# GasSensorCentral_v2_4.net
KiCad netlist of a schematic drawn in EAGLE
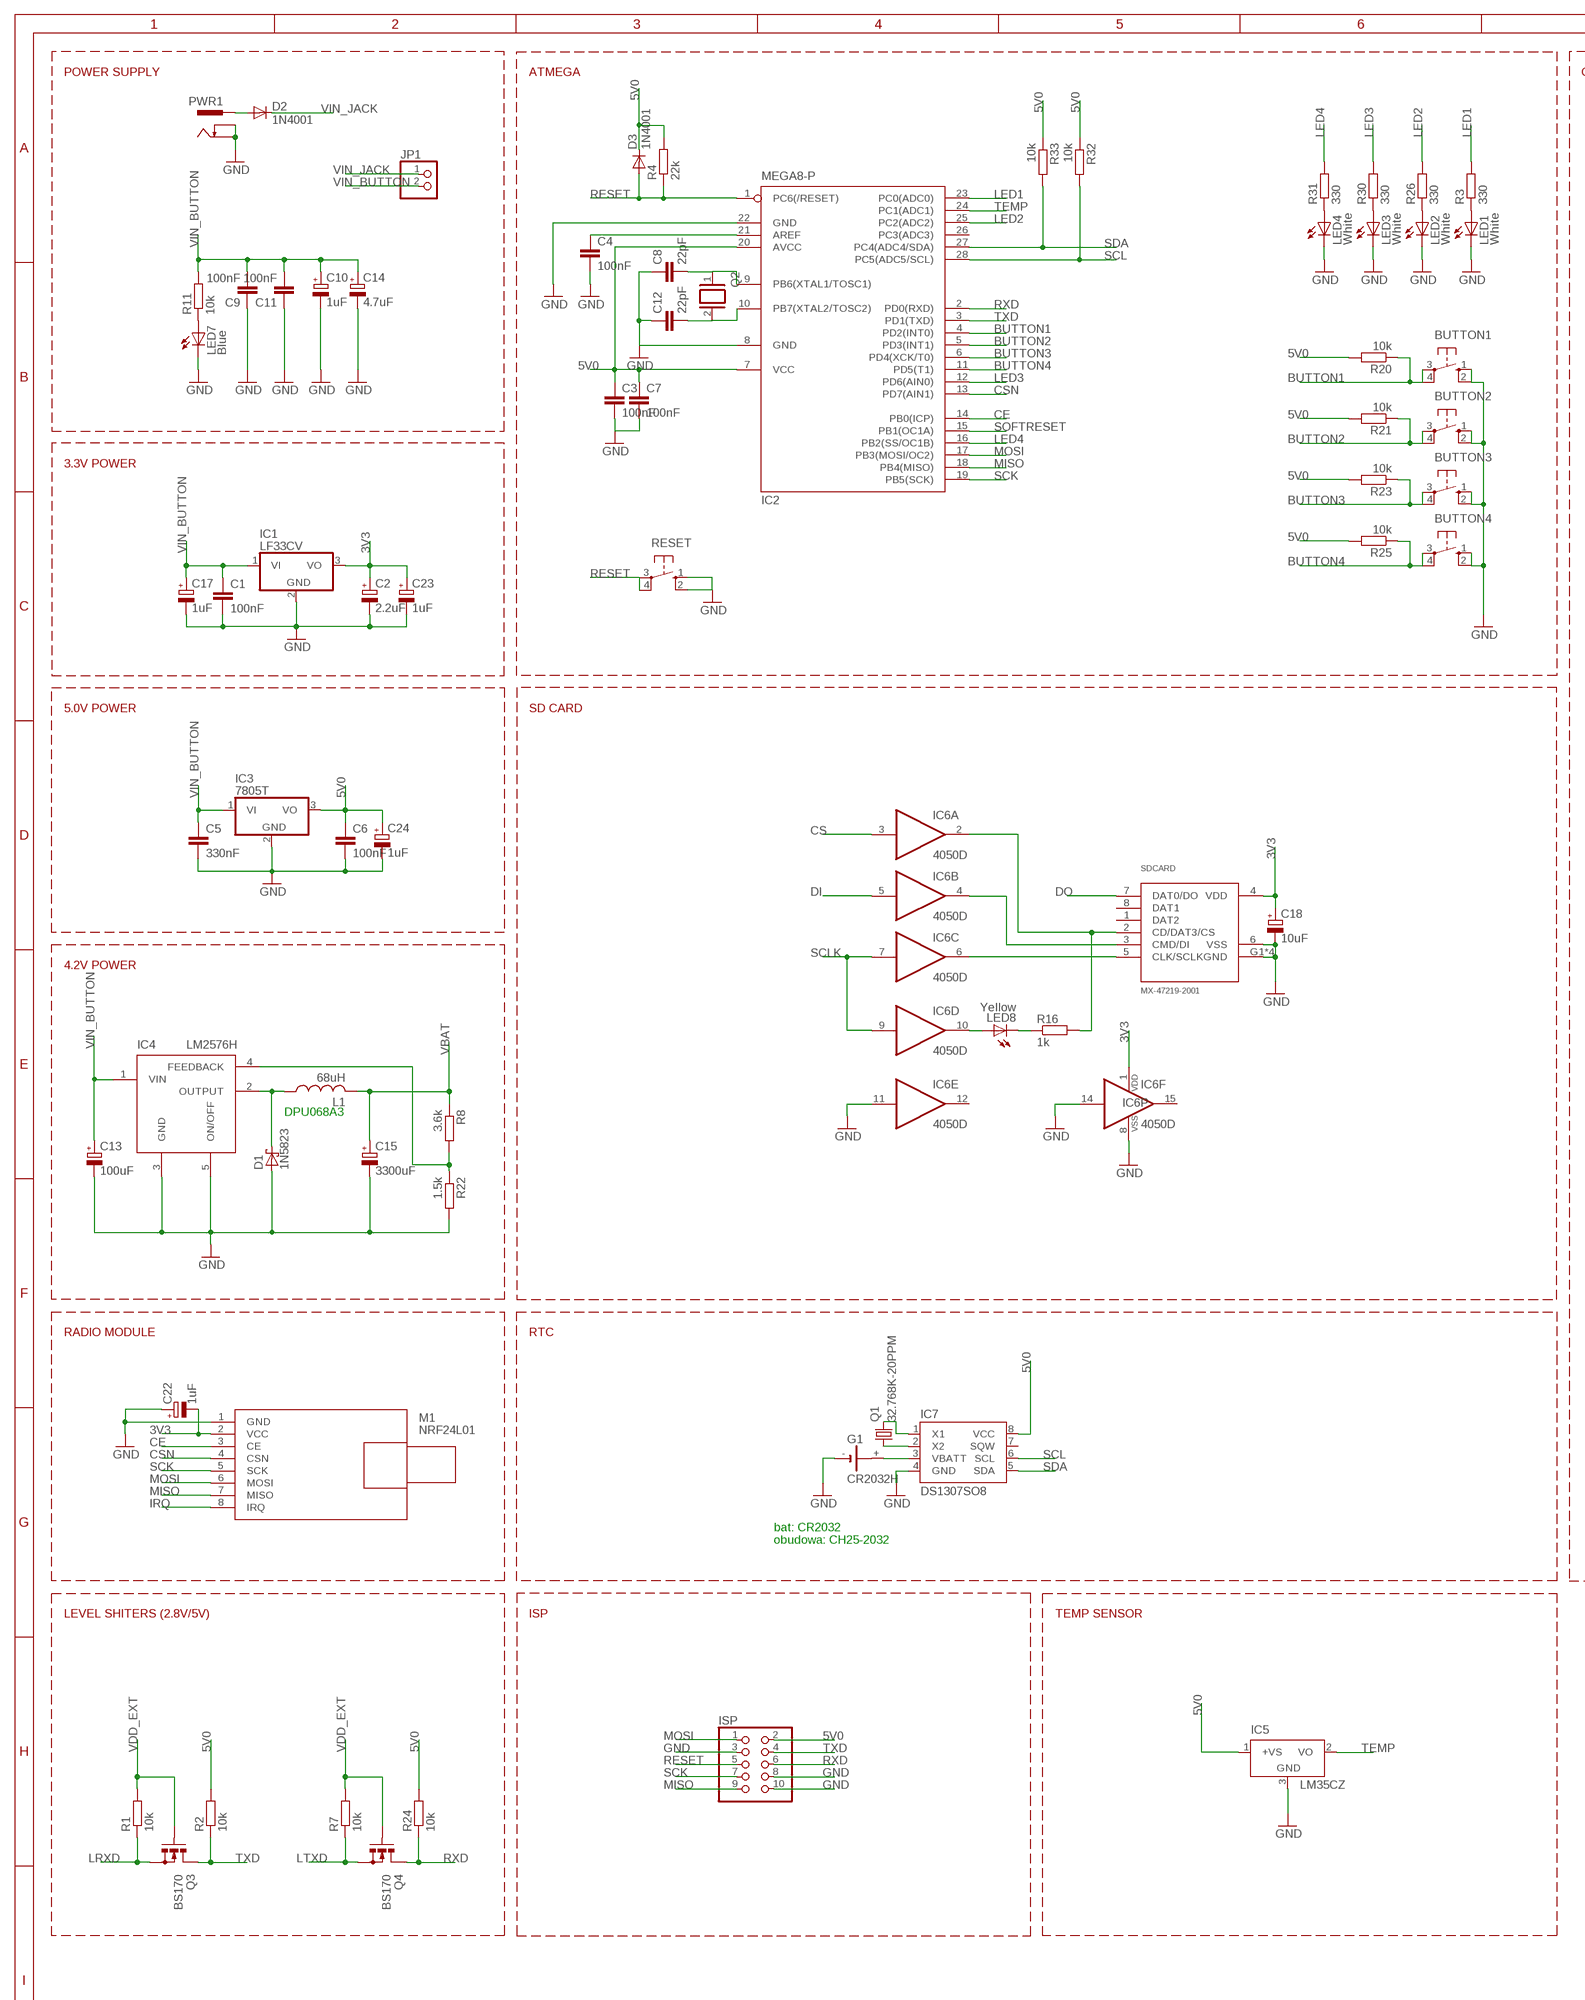
[diagram p0: schematic, sheet 1, part 1 of 2]
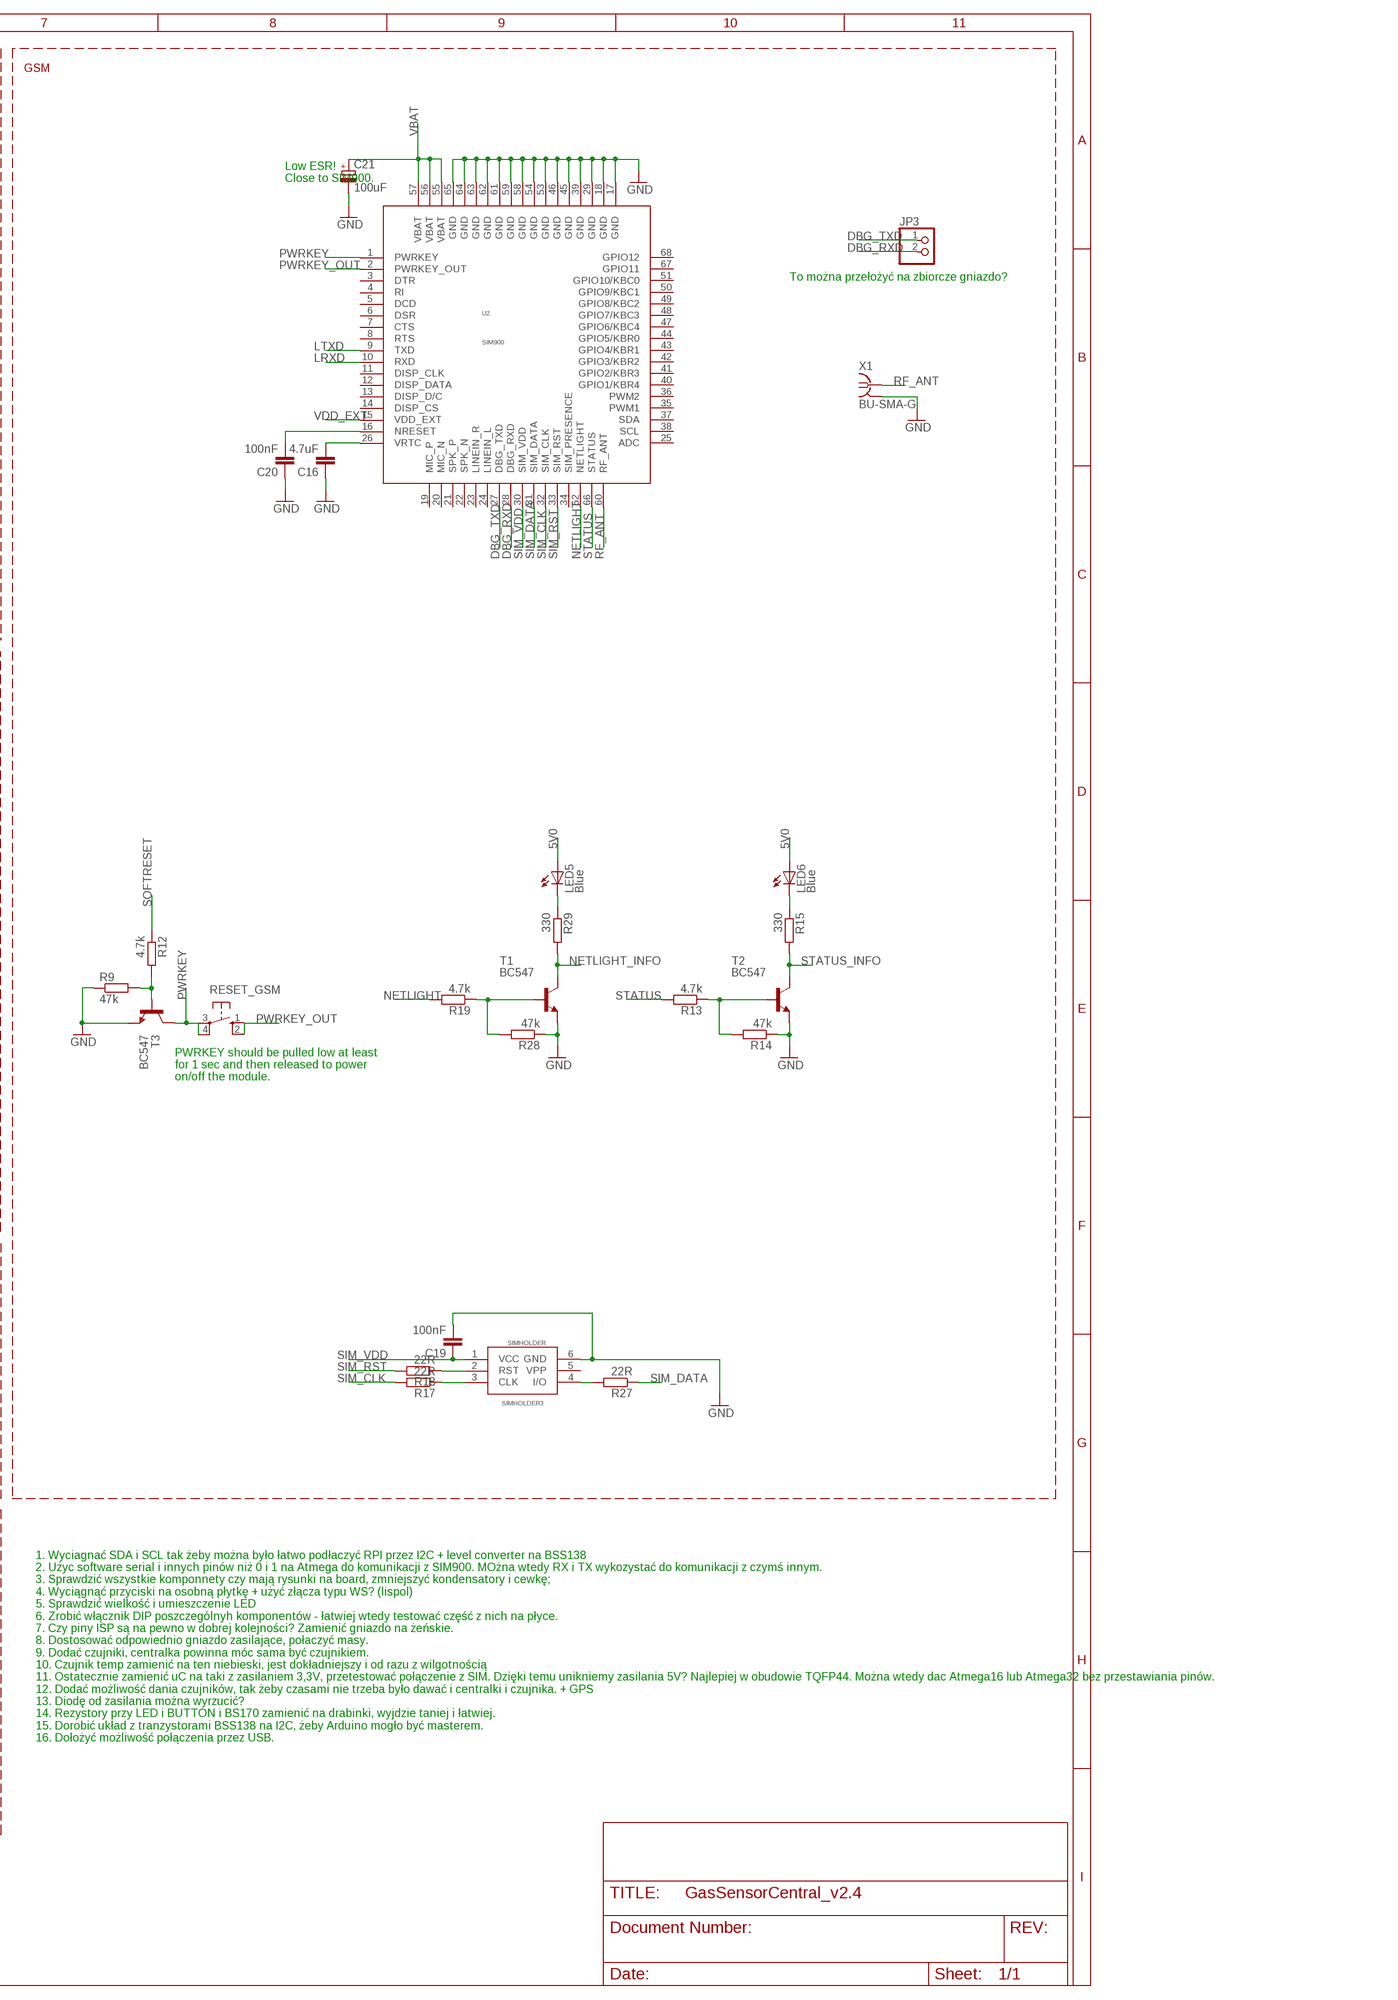
[diagram p1: schematic, sheet 1, part 2 of 2]

(export (version "E")
  (design (tool "Eeschema 10.0.6"))
  (components
    (comp (ref "BUTTON1")
      (value "10-XX")
      (footprint "eagle-import:B3F-10XX")
      (fields (field (name "MPN") "B3F-1000"))
      (libsource (lib "eagle-import") (part "10-XX"))
    )
    (comp (ref "BUTTON2")
      (value "10-XX")
      (footprint "eagle-import:B3F-10XX")
      (fields (field (name "MPN") "B3F-1000"))
      (libsource (lib "eagle-import") (part "10-XX"))
    )
    (comp (ref "BUTTON3")
      (value "10-XX")
      (footprint "eagle-import:B3F-10XX")
      (fields (field (name "MPN") "B3F-1000"))
      (libsource (lib "eagle-import") (part "10-XX"))
    )
    (comp (ref "BUTTON4")
      (value "10-XX")
      (footprint "eagle-import:B3F-10XX")
      (fields (field (name "MPN") "B3F-1000"))
      (libsource (lib "eagle-import") (part "10-XX"))
    )
    (comp (ref "C1")
      (value "100nF")
      (footprint "eagle-import:C025-025X050")
      (libsource (lib "eagle-import") (part "C-EU025-025X050"))
    )
    (comp (ref "C2")
      (value "2.2uF")
      (footprint "eagle-import:E2,5-5")
      (libsource (lib "eagle-import") (part "CPOL-EUE2.5-5"))
    )
    (comp (ref "C3")
      (value "100nF")
      (footprint "eagle-import:C025-025X050")
      (libsource (lib "eagle-import") (part "C-EU025-025X050"))
    )
    (comp (ref "C4")
      (value "100nF")
      (footprint "eagle-import:C025-025X050")
      (libsource (lib "eagle-import") (part "C-EU025-025X050"))
    )
    (comp (ref "C5")
      (value "330nF")
      (footprint "eagle-import:C025-025X050")
      (libsource (lib "eagle-import") (part "C-EU025-025X050"))
    )
    (comp (ref "C6")
      (value "100nF")
      (footprint "eagle-import:C025-025X050")
      (libsource (lib "eagle-import") (part "C-EU025-025X050"))
    )
    (comp (ref "C7")
      (value "100nF")
      (footprint "eagle-import:C025-025X050")
      (libsource (lib "eagle-import") (part "C-EU025-025X050"))
    )
    (comp (ref "C8")
      (value "22pF")
      (footprint "eagle-import:C025-025X050")
      (libsource (lib "eagle-import") (part "C-EU025-025X050"))
    )
    (comp (ref "C9")
      (value "100nF")
      (footprint "eagle-import:C025-025X050")
      (libsource (lib "eagle-import") (part "C-EU025-025X050"))
    )
    (comp (ref "C10")
      (value "1uF")
      (footprint "eagle-import:E2,5-5")
      (libsource (lib "eagle-import") (part "CPOL-EUE2.5-5"))
    )
    (comp (ref "C11")
      (value "100nF")
      (footprint "eagle-import:C025-025X050")
      (libsource (lib "eagle-import") (part "C-EU025-025X050"))
    )
    (comp (ref "C12")
      (value "22pF")
      (footprint "eagle-import:C025-025X050")
      (libsource (lib "eagle-import") (part "C-EU025-025X050"))
    )
    (comp (ref "C13")
      (value "100uF")
      (footprint "eagle-import:E2,5-5")
      (libsource (lib "eagle-import") (part "CPOL-EUE2.5-5"))
    )
    (comp (ref "C14")
      (value "4.7uF")
      (footprint "eagle-import:E2,5-5")
      (libsource (lib "eagle-import") (part "CPOL-EUE2.5-5"))
    )
    (comp (ref "C15")
      (value "3300uF")
      (footprint "eagle-import:E5-13")
      (libsource (lib "eagle-import") (part "CPOL-EUE5-13"))
    )
    (comp (ref "C16")
      (value "4.7uF")
      (footprint "eagle-import:C025-025X050")
      (libsource (lib "eagle-import") (part "C-EU025-025X050"))
    )
    (comp (ref "C17")
      (value "1uF")
      (footprint "eagle-import:E2,5-5")
      (libsource (lib "eagle-import") (part "CPOL-EUE2.5-5"))
    )
    (comp (ref "C18")
      (value "10uF")
      (footprint "eagle-import:E2,5-5")
      (libsource (lib "eagle-import") (part "CPOL-EUE2.5-5"))
    )
    (comp (ref "C19")
      (value "100nF")
      (footprint "eagle-import:C025-025X050")
      (libsource (lib "eagle-import") (part "C-EU025-025X050"))
    )
    (comp (ref "C20")
      (value "100nF")
      (footprint "eagle-import:C025-025X050")
      (libsource (lib "eagle-import") (part "C-EU025-025X050"))
    )
    (comp (ref "C21")
      (value "100uF")
      (footprint "eagle-import:E2,5-5")
      (libsource (lib "eagle-import") (part "CPOL-EUE2.5-5"))
    )
    (comp (ref "C22")
      (value "1uF")
      (footprint "eagle-import:E2,5-5")
      (libsource (lib "eagle-import") (part "CPOL-EUE2.5-5"))
    )
    (comp (ref "C23")
      (value "1uF")
      (footprint "eagle-import:E2,5-5")
      (libsource (lib "eagle-import") (part "CPOL-EUE2.5-5"))
    )
    (comp (ref "C24")
      (value "1uF")
      (footprint "eagle-import:E2,5-5")
      (libsource (lib "eagle-import") (part "CPOL-EUE2.5-5"))
    )
    (comp (ref "D1")
      (value "1N5823")
      (footprint "eagle-import:DO41-7.6")
      (libsource (lib "eagle-import") (part "1N5817-B"))
    )
    (comp (ref "D2")
      (value "1N4001")
      (footprint "eagle-import:DO41-10")
      (libsource (lib "eagle-import") (part "1N4004"))
    )
    (comp (ref "D3")
      (value "1N4001")
      (footprint "eagle-import:DO41-10")
      (libsource (lib "eagle-import") (part "1N4004"))
    )
    (comp (ref "G1")
      (value "CR2032H")
      (footprint "eagle-import:CR2032H")
      (libsource (lib "eagle-import") (part "CR2032H"))
    )
    (comp (ref "IC1")
      (value "LF33CV")
      (footprint "eagle-import:TO220H")
      (libsource (lib "eagle-import") (part "78T05"))
    )
    (comp (ref "IC2")
      (value "MEGA8-P")
      (footprint "eagle-import:DIL28-3")
      (libsource (lib "eagle-import") (part "MEGA8-P"))
    )
    (comp (ref "IC3")
      (value "7805T")
      (footprint "eagle-import:TO220H")
      (libsource (lib "eagle-import") (part "78T05"))
    )
    (comp (ref "IC4")
      (value "LM2576H")
      (footprint "eagle-import:TO220-52")
      (libsource (lib "eagle-import") (part "LM2576H"))
    )
    (comp (ref "IC5")
      (value "LM35CZ")
      (footprint "eagle-import:TO92")
      (libsource (lib "eagle-import") (part "LM35CZ"))
    )
    (comp (ref "IC6")
      (value "4050D")
      (footprint "eagle-import:SO16")
      (libsource (lib "eagle-import") (part "4050D"))
    )
    (comp (ref "IC7")
      (value "DS1307SO8")
      (footprint "eagle-import:SO08")
      (libsource (lib "eagle-import") (part "DS1307SO8"))
    )
    (comp (ref "ISP")
      (value "PINHD-2X5")
      (footprint "eagle-import:2X05")
      (libsource (lib "eagle-import") (part "PINHD-2X5"))
    )
    (comp (ref "JP1")
      (value "PINHD-1X2")
      (footprint "eagle-import:1X02")
      (libsource (lib "eagle-import") (part "PINHD-1X2"))
    )
    (comp (ref "JP3")
      (value "PINHD-1X2")
      (footprint "eagle-import:1X02")
      (libsource (lib "eagle-import") (part "PINHD-1X2"))
    )
    (comp (ref "L1")
      (value "68uH")
      (footprint "eagle-import:TJ4-U1")
      (libsource (lib "eagle-import") (part "L-USTJ4-U1"))
    )
    (comp (ref "LED1")
      (value "White")
      (footprint "eagle-import:LED3MM")
      (libsource (lib "eagle-import") (part "LED3MM"))
    )
    (comp (ref "LED2")
      (value "White")
      (footprint "eagle-import:LED3MM")
      (libsource (lib "eagle-import") (part "LED3MM"))
    )
    (comp (ref "LED3")
      (value "White")
      (footprint "eagle-import:LED3MM")
      (libsource (lib "eagle-import") (part "LED3MM"))
    )
    (comp (ref "LED4")
      (value "White")
      (footprint "eagle-import:LED3MM")
      (libsource (lib "eagle-import") (part "LED3MM"))
    )
    (comp (ref "LED5")
      (value "Blue")
      (footprint "eagle-import:LED3MM")
      (libsource (lib "eagle-import") (part "LED3MM"))
    )
    (comp (ref "LED6")
      (value "Blue")
      (footprint "eagle-import:LED3MM")
      (libsource (lib "eagle-import") (part "LED3MM"))
    )
    (comp (ref "LED7")
      (value "Blue")
      (footprint "eagle-import:LED3MM")
      (libsource (lib "eagle-import") (part "LED3MM"))
    )
    (comp (ref "LED8")
      (value "Yellow")
      (footprint "eagle-import:LED3MM")
      (libsource (lib "eagle-import") (part "LED3MM"))
    )
    (comp (ref "M1")
      (value "NRF24L01")
      (footprint "eagle-import:WIRELESS-NRD24L01-PA-EXT")
      (libsource (lib "eagle-import") (part "WIRELESS-NRF24L01-PA-EXT"))
    )
    (comp (ref "PWR1")
      (value "PWR-JAKPWR_JACK_UNI_MILLING")
      (footprint "eagle-import:PWR_JACK_UNI_MILLING")
      (libsource (lib "eagle-import") (part "PWR-JAKPWR_JACK_UNI_MILLING"))
    )
    (comp (ref "Q1")
      (value "32.768K-20PPM")
      (footprint "eagle-import:TC26V")
      (libsource (lib "eagle-import") (part "CRYSTALTC26V"))
    )
    (comp (ref "Q2")
      (value "XTAL/S")
      (footprint "eagle-import:QS")
      (libsource (lib "eagle-import") (part "XTAL/S"))
    )
    (comp (ref "Q3")
      (value "BS170")
      (footprint "eagle-import:SOT54E")
      (libsource (lib "eagle-import") (part "BS170"))
    )
    (comp (ref "Q4")
      (value "BS170")
      (footprint "eagle-import:SOT54E")
      (libsource (lib "eagle-import") (part "BS170"))
    )
    (comp (ref "R1")
      (value "10k")
      (footprint "eagle-import:0207_10")
      (libsource (lib "eagle-import") (part "R-EU_0207/10"))
    )
    (comp (ref "R2")
      (value "10k")
      (footprint "eagle-import:0207_10")
      (libsource (lib "eagle-import") (part "R-EU_0207/10"))
    )
    (comp (ref "R3")
      (value "330")
      (footprint "eagle-import:0207_10")
      (libsource (lib "eagle-import") (part "R-EU_0207/10"))
    )
    (comp (ref "R4")
      (value "22k")
      (footprint "eagle-import:0207_10")
      (libsource (lib "eagle-import") (part "R-EU_0207/10"))
    )
    (comp (ref "R7")
      (value "10k")
      (footprint "eagle-import:0207_10")
      (libsource (lib "eagle-import") (part "R-EU_0207/10"))
    )
    (comp (ref "R8")
      (value "3.6k")
      (footprint "eagle-import:0207_10")
      (libsource (lib "eagle-import") (part "R-EU_0207/10"))
    )
    (comp (ref "R9")
      (value "47k")
      (footprint "eagle-import:0207_10")
      (libsource (lib "eagle-import") (part "R-EU_0207/10"))
    )
    (comp (ref "R11")
      (value "10k")
      (footprint "eagle-import:0207_10")
      (libsource (lib "eagle-import") (part "R-EU_0207/10"))
    )
    (comp (ref "R12")
      (value "4.7k")
      (footprint "eagle-import:0207_10")
      (libsource (lib "eagle-import") (part "R-EU_0207/10"))
    )
    (comp (ref "R13")
      (value "4.7k")
      (footprint "eagle-import:0207_10")
      (libsource (lib "eagle-import") (part "R-EU_0207/10"))
    )
    (comp (ref "R14")
      (value "47k")
      (footprint "eagle-import:0207_10")
      (libsource (lib "eagle-import") (part "R-EU_0207/10"))
    )
    (comp (ref "R15")
      (value "330")
      (footprint "eagle-import:0207_10")
      (libsource (lib "eagle-import") (part "R-EU_0207/10"))
    )
    (comp (ref "R16")
      (value "1k")
      (footprint "eagle-import:0207_10")
      (libsource (lib "eagle-import") (part "R-EU_0207/10"))
    )
    (comp (ref "R17")
      (value "22R")
      (footprint "eagle-import:0207_10")
      (libsource (lib "eagle-import") (part "R-EU_0207/10"))
    )
    (comp (ref "R18")
      (value "22R")
      (footprint "eagle-import:0207_10")
      (libsource (lib "eagle-import") (part "R-EU_0207/10"))
    )
    (comp (ref "R19")
      (value "4.7k")
      (footprint "eagle-import:0207_10")
      (libsource (lib "eagle-import") (part "R-EU_0207/10"))
    )
    (comp (ref "R20")
      (value "10k")
      (footprint "eagle-import:0207_10")
      (libsource (lib "eagle-import") (part "R-EU_0207/10"))
    )
    (comp (ref "R21")
      (value "10k")
      (footprint "eagle-import:0207_10")
      (libsource (lib "eagle-import") (part "R-EU_0207/10"))
    )
    (comp (ref "R22")
      (value "1.5k")
      (footprint "eagle-import:0207_10")
      (libsource (lib "eagle-import") (part "R-EU_0207/10"))
    )
    (comp (ref "R23")
      (value "10k")
      (footprint "eagle-import:0207_10")
      (libsource (lib "eagle-import") (part "R-EU_0207/10"))
    )
    (comp (ref "R24")
      (value "10k")
      (footprint "eagle-import:0207_10")
      (libsource (lib "eagle-import") (part "R-EU_0207/10"))
    )
    (comp (ref "R25")
      (value "10k")
      (footprint "eagle-import:0207_10")
      (libsource (lib "eagle-import") (part "R-EU_0207/10"))
    )
    (comp (ref "R26")
      (value "330")
      (footprint "eagle-import:0207_10")
      (libsource (lib "eagle-import") (part "R-EU_0207/10"))
    )
    (comp (ref "R27")
      (value "22R")
      (footprint "eagle-import:0207_10")
      (libsource (lib "eagle-import") (part "R-EU_0207/10"))
    )
    (comp (ref "R28")
      (value "47k")
      (footprint "eagle-import:0207_10")
      (libsource (lib "eagle-import") (part "R-EU_0207/10"))
    )
    (comp (ref "R29")
      (value "330")
      (footprint "eagle-import:0207_10")
      (libsource (lib "eagle-import") (part "R-EU_0207/10"))
    )
    (comp (ref "R30")
      (value "330")
      (footprint "eagle-import:0207_10")
      (libsource (lib "eagle-import") (part "R-EU_0207/10"))
    )
    (comp (ref "R31")
      (value "330")
      (footprint "eagle-import:0207_10")
      (libsource (lib "eagle-import") (part "R-EU_0207/10"))
    )
    (comp (ref "R32")
      (value "10k")
      (footprint "eagle-import:0207_10")
      (libsource (lib "eagle-import") (part "R-EU_0207/10"))
    )
    (comp (ref "R33")
      (value "10k")
      (footprint "eagle-import:0207_10")
      (libsource (lib "eagle-import") (part "R-EU_0207/10"))
    )
    (comp (ref "RESET")
      (value "10-XX")
      (footprint "eagle-import:B3F-10XX")
      (fields (field (name "MPN") "B3F-1000"))
      (libsource (lib "eagle-import") (part "10-XX"))
    )
    (comp (ref "RESET_GSM")
      (value "10-XX")
      (footprint "eagle-import:B3F-10XX")
      (fields (field (name "MPN") "B3F-1000"))
      (libsource (lib "eagle-import") (part "10-XX"))
    )
    (comp (ref "SDCARD")
      (value "MX-47219-2001")
      (footprint "eagle-import:MX-47219-2001")
      (libsource (lib "eagle-import") (part "MX-47219-2001"))
    )
    (comp (ref "SIMHOLDER")
      (value "SIMHOLDER3")
      (footprint "eagle-import:SIMHOLDER3")
      (libsource (lib "eagle-import") (part "SIMHOLDER3"))
    )
    (comp (ref "T1")
      (value "BC547")
      (footprint "eagle-import:TO92")
      (libsource (lib "eagle-import") (part "BC547"))
    )
    (comp (ref "T2")
      (value "BC547")
      (footprint "eagle-import:TO92")
      (libsource (lib "eagle-import") (part "BC547"))
    )
    (comp (ref "T3")
      (value "BC547")
      (footprint "eagle-import:TO92")
      (libsource (lib "eagle-import") (part "BC547"))
    )
    (comp (ref "U2")
      (value "SIM900")
      (footprint "eagle-import:SIM900")
      (libsource (lib "eagle-import") (part "SIM900"))
    )
    (comp (ref "X1")
      (value "BU-SMA-G")
      (footprint "eagle-import:BU-SMA-G")
      (libsource (lib "eagle-import") (part "BU-SMA-G"))
    )
  )
  (nets
    (net (code "1") (name "/3V3") (class "Default")
      (node (ref "C18") (pin "+") (pinfunction "+_+") (pintype "passive"))
      (node (ref "C2") (pin "+") (pinfunction "+_+") (pintype "passive"))
      (node (ref "C22") (pin "-") (pinfunction "-_-") (pintype "passive"))
      (node (ref "C23") (pin "+") (pinfunction "+_+") (pintype "passive"))
      (node (ref "IC1") (pin "3") (pinfunction "VO_3") (pintype "passive"))
      (node (ref "IC6") (pin "1") (pinfunction "VDD_1") (pintype "power_in"))
      (node (ref "M1") (pin "2") (pinfunction "VCC_2") (pintype "power_in"))
      (node (ref "SDCARD") (pin "4") (pinfunction "VDD_4") (pintype "bidirectional"))
    )
    (net (code "2") (name "/5V0") (class "Default")
      (node (ref "C24") (pin "+") (pinfunction "+_+") (pintype "passive"))
      (node (ref "C3") (pin "1") (pinfunction "1_1") (pintype "passive"))
      (node (ref "C6") (pin "1") (pinfunction "1_1") (pintype "passive"))
      (node (ref "C7") (pin "1") (pinfunction "1_1") (pintype "passive"))
      (node (ref "D3") (pin "C") (pinfunction "C_C") (pintype "passive"))
      (node (ref "IC2") (pin "20") (pinfunction "AVCC_20") (pintype "power_in"))
      (node (ref "IC2") (pin "7") (pinfunction "VCC_7") (pintype "power_in"))
      (node (ref "IC3") (pin "3") (pinfunction "VO_3") (pintype "passive"))
      (node (ref "IC5") (pin "1") (pinfunction "+VS_1") (pintype "input"))
      (node (ref "IC7") (pin "8") (pinfunction "VCC_8") (pintype "bidirectional"))
      (node (ref "ISP") (pin "2") (pinfunction "2_2") (pintype "passive"))
      (node (ref "LED5") (pin "A") (pinfunction "A_A") (pintype "passive"))
      (node (ref "LED6") (pin "A") (pinfunction "A_A") (pintype "passive"))
      (node (ref "R2") (pin "2") (pinfunction "2_2") (pintype "passive"))
      (node (ref "R20") (pin "2") (pinfunction "2_2") (pintype "passive"))
      (node (ref "R21") (pin "2") (pinfunction "2_2") (pintype "passive"))
      (node (ref "R23") (pin "2") (pinfunction "2_2") (pintype "passive"))
      (node (ref "R24") (pin "2") (pinfunction "2_2") (pintype "passive"))
      (node (ref "R25") (pin "2") (pinfunction "2_2") (pintype "passive"))
      (node (ref "R32") (pin "1") (pinfunction "1_1") (pintype "passive"))
      (node (ref "R33") (pin "1") (pinfunction "1_1") (pintype "passive"))
      (node (ref "R4") (pin "2") (pinfunction "2_2") (pintype "passive"))
    )
    (net (code "3") (name "/BUTTON1") (class "Default")
      (node (ref "BUTTON1") (pin "3") (pinfunction "P_3") (pintype "passive"))
      (node (ref "BUTTON1") (pin "4") (pinfunction "P1_4") (pintype "passive"))
      (node (ref "IC2") (pin "4") (pinfunction "PD2(INT0)_4") (pintype "bidirectional"))
      (node (ref "R20") (pin "1") (pinfunction "1_1") (pintype "passive"))
    )
    (net (code "4") (name "/BUTTON2") (class "Default")
      (node (ref "BUTTON2") (pin "3") (pinfunction "P_3") (pintype "passive"))
      (node (ref "BUTTON2") (pin "4") (pinfunction "P1_4") (pintype "passive"))
      (node (ref "IC2") (pin "5") (pinfunction "PD3(INT1)_5") (pintype "bidirectional"))
      (node (ref "R21") (pin "1") (pinfunction "1_1") (pintype "passive"))
    )
    (net (code "5") (name "/BUTTON3") (class "Default")
      (node (ref "BUTTON3") (pin "3") (pinfunction "P_3") (pintype "passive"))
      (node (ref "BUTTON3") (pin "4") (pinfunction "P1_4") (pintype "passive"))
      (node (ref "IC2") (pin "6") (pinfunction "PD4(XCK/T0)_6") (pintype "bidirectional"))
      (node (ref "R23") (pin "1") (pinfunction "1_1") (pintype "passive"))
    )
    (net (code "6") (name "/BUTTON4") (class "Default")
      (node (ref "BUTTON4") (pin "3") (pinfunction "P_3") (pintype "passive"))
      (node (ref "BUTTON4") (pin "4") (pinfunction "P1_4") (pintype "passive"))
      (node (ref "IC2") (pin "11") (pinfunction "PD5(T1)_11") (pintype "bidirectional"))
      (node (ref "R25") (pin "1") (pinfunction "1_1") (pintype "passive"))
    )
    (net (code "7") (name "/CE") (class "Default")
      (node (ref "IC2") (pin "14") (pinfunction "PB0(ICP)_14") (pintype "bidirectional"))
      (node (ref "M1") (pin "3") (pinfunction "CE_3") (pintype "bidirectional"))
    )
    (net (code "8") (name "/CS") (class "Default")
      (node (ref "IC6") (pin "3") (pinfunction "I_3") (pintype "input"))
    )
    (net (code "9") (name "/CSN") (class "Default")
      (node (ref "IC2") (pin "13") (pinfunction "PD7(AIN1)_13") (pintype "bidirectional"))
      (node (ref "M1") (pin "4") (pinfunction "CSN_4") (pintype "bidirectional"))
    )
    (net (code "10") (name "/DBG_RXD") (class "Default")
      (node (ref "JP3") (pin "2") (pinfunction "2_2") (pintype "passive"))
      (node (ref "U2") (pin "28") (pinfunction "DBG_RXD_28") (pintype "input"))
    )
    (net (code "11") (name "/DBG_TXD") (class "Default")
      (node (ref "JP3") (pin "1") (pinfunction "1_1") (pintype "passive"))
      (node (ref "U2") (pin "27") (pinfunction "DBG_TXD_27") (pintype "output"))
    )
    (net (code "12") (name "/DI") (class "Default")
      (node (ref "IC6") (pin "5") (pinfunction "I_5") (pintype "input"))
    )
    (net (code "13") (name "/DO") (class "Default")
      (node (ref "SDCARD") (pin "7") (pinfunction "DAT0/DO_7") (pintype "bidirectional"))
    )
    (net (code "14") (name "/IRQ") (class "Default")
      (node (ref "M1") (pin "8") (pinfunction "IRQ_8") (pintype "bidirectional"))
    )
    (net (code "15") (name "/LED1") (class "Default")
      (node (ref "IC2") (pin "23") (pinfunction "PC0(ADC0)_23") (pintype "bidirectional"))
      (node (ref "R3") (pin "2") (pinfunction "2_2") (pintype "passive"))
    )
    (net (code "16") (name "/LED2") (class "Default")
      (node (ref "IC2") (pin "25") (pinfunction "PC2(ADC2)_25") (pintype "bidirectional"))
      (node (ref "R26") (pin "2") (pinfunction "2_2") (pintype "passive"))
    )
    (net (code "17") (name "/LED3") (class "Default")
      (node (ref "IC2") (pin "12") (pinfunction "PD6(AIN0)_12") (pintype "bidirectional"))
      (node (ref "R30") (pin "2") (pinfunction "2_2") (pintype "passive"))
    )
    (net (code "18") (name "/LED4") (class "Default")
      (node (ref "IC2") (pin "16") (pinfunction "PB2(SS/OC1B)_16") (pintype "bidirectional"))
      (node (ref "R31") (pin "2") (pinfunction "2_2") (pintype "passive"))
    )
    (net (code "19") (name "/LRXD") (class "Default")
      (node (ref "Q3") (pin "S") (pinfunction "S_S") (pintype "passive"))
      (node (ref "R1") (pin "1") (pinfunction "1_1") (pintype "passive"))
      (node (ref "U2") (pin "10") (pinfunction "RXD_10") (pintype "input"))
    )
    (net (code "20") (name "/LTXD") (class "Default")
      (node (ref "Q4") (pin "S") (pinfunction "S_S") (pintype "passive"))
      (node (ref "R7") (pin "1") (pinfunction "1_1") (pintype "passive"))
      (node (ref "U2") (pin "9") (pinfunction "TXD_9") (pintype "output"))
    )
    (net (code "21") (name "/MISO") (class "Default")
      (node (ref "IC2") (pin "18") (pinfunction "PB4(MISO)_18") (pintype "bidirectional"))
      (node (ref "ISP") (pin "9") (pinfunction "9_9") (pintype "passive"))
      (node (ref "M1") (pin "7") (pinfunction "MISO_7") (pintype "bidirectional"))
    )
    (net (code "22") (name "/MOSI") (class "Default")
      (node (ref "IC2") (pin "17") (pinfunction "PB3(MOSI/OC2)_17") (pintype "bidirectional"))
      (node (ref "ISP") (pin "1") (pinfunction "1_1") (pintype "passive"))
      (node (ref "M1") (pin "6") (pinfunction "MOSI_6") (pintype "bidirectional"))
    )
    (net (code "23") (name "/NETLIGHT") (class "Default")
      (node (ref "R19") (pin "2") (pinfunction "2_2") (pintype "passive"))
      (node (ref "U2") (pin "52") (pinfunction "NETLIGHT_52") (pintype "output"))
    )
    (net (code "24") (name "/NETLIGHT_INFO") (class "Default")
      (node (ref "R29") (pin "2") (pinfunction "2_2") (pintype "passive"))
      (node (ref "T1") (pin "3") (pinfunction "C_3") (pintype "passive"))
    )
    (net (code "25") (name "/PWRKEY") (class "Default")
      (node (ref "RESET_GSM") (pin "3") (pinfunction "P_3") (pintype "passive"))
      (node (ref "RESET_GSM") (pin "4") (pinfunction "P1_4") (pintype "passive"))
      (node (ref "T3") (pin "3") (pinfunction "C_3") (pintype "passive"))
      (node (ref "U2") (pin "1") (pinfunction "PWRKEY_1") (pintype "input"))
    )
    (net (code "26") (name "/PWRKEY_OUT") (class "Default")
      (node (ref "RESET_GSM") (pin "1") (pinfunction "S_1") (pintype "passive"))
      (node (ref "RESET_GSM") (pin "2") (pinfunction "S1_2") (pintype "passive"))
      (node (ref "U2") (pin "2") (pinfunction "PWRKEY_OUT_2") (pintype "output"))
    )
    (net (code "27") (name "/RESET") (class "Default")
      (node (ref "D3") (pin "A") (pinfunction "A_A") (pintype "passive"))
      (node (ref "IC2") (pin "1") (pinfunction "PC6(/RESET)_1") (pintype "bidirectional"))
      (node (ref "ISP") (pin "5") (pinfunction "5_5") (pintype "passive"))
      (node (ref "R4") (pin "1") (pinfunction "1_1") (pintype "passive"))
      (node (ref "RESET") (pin "3") (pinfunction "P_3") (pintype "passive"))
      (node (ref "RESET") (pin "4") (pinfunction "P1_4") (pintype "passive"))
    )
    (net (code "28") (name "/RF_ANT") (class "Default")
      (node (ref "U2") (pin "60") (pinfunction "RF_ANT_60") (pintype "bidirectional"))
      (node (ref "X1") (pin "1") (pinfunction "1_1") (pintype "passive"))
    )
    (net (code "29") (name "/RXD") (class "Default")
      (node (ref "IC2") (pin "2") (pinfunction "PD0(RXD)_2") (pintype "bidirectional"))
      (node (ref "ISP") (pin "6") (pinfunction "6_6") (pintype "passive"))
      (node (ref "Q4") (pin "D") (pinfunction "D_D") (pintype "passive"))
      (node (ref "R24") (pin "1") (pinfunction "1_1") (pintype "passive"))
    )
    (net (code "30") (name "/SCK") (class "Default")
      (node (ref "IC2") (pin "19") (pinfunction "PB5(SCK)_19") (pintype "bidirectional"))
      (node (ref "ISP") (pin "7") (pinfunction "7_7") (pintype "passive"))
      (node (ref "M1") (pin "5") (pinfunction "SCK_5") (pintype "bidirectional"))
    )
    (net (code "31") (name "/SCL") (class "Default")
      (node (ref "IC2") (pin "28") (pinfunction "PC5(ADC5/SCL)_28") (pintype "bidirectional"))
      (node (ref "IC7") (pin "6") (pinfunction "SCL_6") (pintype "bidirectional"))
      (node (ref "R32") (pin "2") (pinfunction "2_2") (pintype "passive"))
    )
    (net (code "32") (name "/SCLK") (class "Default")
      (node (ref "IC6") (pin "7") (pinfunction "I_7") (pintype "input"))
      (node (ref "IC6") (pin "9") (pinfunction "I_9") (pintype "input"))
    )
    (net (code "33") (name "/SDA") (class "Default")
      (node (ref "IC2") (pin "27") (pinfunction "PC4(ADC4/SDA)_27") (pintype "bidirectional"))
      (node (ref "IC7") (pin "5") (pinfunction "SDA_5") (pintype "bidirectional"))
      (node (ref "R33") (pin "2") (pinfunction "2_2") (pintype "passive"))
    )
    (net (code "34") (name "/SIM_CLK") (class "Default")
      (node (ref "R17") (pin "2") (pinfunction "2_2") (pintype "passive"))
      (node (ref "U2") (pin "32") (pinfunction "SIM_CLK_32") (pintype "output"))
    )
    (net (code "35") (name "/SIM_DATA") (class "Default")
      (node (ref "R27") (pin "1") (pinfunction "1_1") (pintype "passive"))
      (node (ref "U2") (pin "31") (pinfunction "SIM_DATA_31") (pintype "bidirectional"))
    )
    (net (code "36") (name "/SIM_RST") (class "Default")
      (node (ref "R18") (pin "2") (pinfunction "2_2") (pintype "passive"))
      (node (ref "U2") (pin "33") (pinfunction "SIM_RST_33") (pintype "output"))
    )
    (net (code "37") (name "/SIM_VDD") (class "Default")
      (node (ref "C19") (pin "1") (pinfunction "1_1") (pintype "passive"))
      (node (ref "SIMHOLDER") (pin "1") (pinfunction "VCC_1") (pintype "bidirectional"))
      (node (ref "U2") (pin "30") (pinfunction "SIM_VDD_30") (pintype "output"))
    )
    (net (code "38") (name "/SOFTRESET") (class "Default")
      (node (ref "IC2") (pin "15") (pinfunction "PB1(OC1A)_15") (pintype "bidirectional"))
      (node (ref "R12") (pin "1") (pinfunction "1_1") (pintype "passive"))
    )
    (net (code "39") (name "/STATUS") (class "Default")
      (node (ref "R13") (pin "2") (pinfunction "2_2") (pintype "passive"))
      (node (ref "U2") (pin "66") (pinfunction "STATUS_66") (pintype "output"))
    )
    (net (code "40") (name "/STATUS_INFO") (class "Default")
      (node (ref "R15") (pin "2") (pinfunction "2_2") (pintype "passive"))
      (node (ref "T2") (pin "3") (pinfunction "C_3") (pintype "passive"))
    )
    (net (code "41") (name "/TEMP") (class "Default")
      (node (ref "IC2") (pin "24") (pinfunction "PC1(ADC1)_24") (pintype "bidirectional"))
      (node (ref "IC5") (pin "2") (pinfunction "VO_2") (pintype "input"))
    )
    (net (code "42") (name "/TXD") (class "Default")
      (node (ref "IC2") (pin "3") (pinfunction "PD1(TXD)_3") (pintype "bidirectional"))
      (node (ref "ISP") (pin "4") (pinfunction "4_4") (pintype "passive"))
      (node (ref "Q3") (pin "D") (pinfunction "D_D") (pintype "passive"))
      (node (ref "R2") (pin "1") (pinfunction "1_1") (pintype "passive"))
    )
    (net (code "43") (name "/VBAT") (class "Default")
      (node (ref "C15") (pin "+") (pinfunction "+_+") (pintype "passive"))
      (node (ref "C21") (pin "+") (pinfunction "+_+") (pintype "passive"))
      (node (ref "L1") (pin "2") (pinfunction "2_2") (pintype "passive"))
      (node (ref "R8") (pin "1") (pinfunction "1_1") (pintype "passive"))
      (node (ref "U2") (pin "55") (pinfunction "VBAT_55") (pintype "power_in"))
      (node (ref "U2") (pin "56") (pinfunction "VBAT_56") (pintype "power_in"))
      (node (ref "U2") (pin "57") (pinfunction "VBAT_57") (pintype "power_in"))
    )
    (net (code "44") (name "/VDD_EXT") (class "Default")
      (node (ref "Q3") (pin "G") (pinfunction "G_G") (pintype "passive"))
      (node (ref "Q4") (pin "G") (pinfunction "G_G") (pintype "passive"))
      (node (ref "R1") (pin "2") (pinfunction "2_2") (pintype "passive"))
      (node (ref "R7") (pin "2") (pinfunction "2_2") (pintype "passive"))
      (node (ref "U2") (pin "15") (pinfunction "VDD_EXT_15") (pintype "output"))
    )
    (net (code "45") (name "/VIN_BUTTON") (class "Default")
      (node (ref "C1") (pin "1") (pinfunction "1_1") (pintype "passive"))
      (node (ref "C10") (pin "+") (pinfunction "+_+") (pintype "passive"))
      (node (ref "C11") (pin "2") (pinfunction "2_2") (pintype "passive"))
      (node (ref "C13") (pin "+") (pinfunction "+_+") (pintype "passive"))
      (node (ref "C14") (pin "+") (pinfunction "+_+") (pintype "passive"))
      (node (ref "C17") (pin "+") (pinfunction "+_+") (pintype "passive"))
      (node (ref "C5") (pin "1") (pinfunction "1_1") (pintype "passive"))
      (node (ref "C9") (pin "2") (pinfunction "2_2") (pintype "passive"))
      (node (ref "IC1") (pin "1") (pinfunction "VI_1") (pintype "input"))
      (node (ref "IC3") (pin "1") (pinfunction "VI_1") (pintype "input"))
      (node (ref "IC4") (pin "1") (pinfunction "VIN_1") (pintype "input"))
      (node (ref "JP1") (pin "2") (pinfunction "2_2") (pintype "passive"))
      (node (ref "R11") (pin "2") (pinfunction "2_2") (pintype "passive"))
    )
    (net (code "46") (name "/VIN_JACK") (class "Default")
      (node (ref "D2") (pin "C") (pinfunction "C_C") (pintype "passive"))
      (node (ref "JP1") (pin "1") (pinfunction "1_1") (pintype "passive"))
    )
    (net (code "47") (name "GND") (class "Default")
      (node (ref "BUTTON1") (pin "1") (pinfunction "S_1") (pintype "passive"))
      (node (ref "BUTTON1") (pin "2") (pinfunction "S1_2") (pintype "passive"))
      (node (ref "BUTTON2") (pin "1") (pinfunction "S_1") (pintype "passive"))
      (node (ref "BUTTON2") (pin "2") (pinfunction "S1_2") (pintype "passive"))
      (node (ref "BUTTON3") (pin "1") (pinfunction "S_1") (pintype "passive"))
      (node (ref "BUTTON3") (pin "2") (pinfunction "S1_2") (pintype "passive"))
      (node (ref "BUTTON4") (pin "1") (pinfunction "S_1") (pintype "passive"))
      (node (ref "BUTTON4") (pin "2") (pinfunction "S1_2") (pintype "passive"))
      (node (ref "C1") (pin "2") (pinfunction "2_2") (pintype "passive"))
      (node (ref "C10") (pin "-") (pinfunction "-_-") (pintype "passive"))
      (node (ref "C11") (pin "1") (pinfunction "1_1") (pintype "passive"))
      (node (ref "C12") (pin "1") (pinfunction "1_1") (pintype "passive"))
      (node (ref "C13") (pin "-") (pinfunction "-_-") (pintype "passive"))
      (node (ref "C14") (pin "-") (pinfunction "-_-") (pintype "passive"))
      (node (ref "C15") (pin "-") (pinfunction "-_-") (pintype "passive"))
      (node (ref "C16") (pin "1") (pinfunction "1_1") (pintype "passive"))
      (node (ref "C17") (pin "-") (pinfunction "-_-") (pintype "passive"))
      (node (ref "C18") (pin "-") (pinfunction "-_-") (pintype "passive"))
      (node (ref "C19") (pin "2") (pinfunction "2_2") (pintype "passive"))
      (node (ref "C2") (pin "-") (pinfunction "-_-") (pintype "passive"))
      (node (ref "C20") (pin "1") (pinfunction "1_1") (pintype "passive"))
      (node (ref "C21") (pin "-") (pinfunction "-_-") (pintype "passive"))
      (node (ref "C22") (pin "+") (pinfunction "+_+") (pintype "passive"))
      (node (ref "C23") (pin "-") (pinfunction "-_-") (pintype "passive"))
      (node (ref "C24") (pin "-") (pinfunction "-_-") (pintype "passive"))
      (node (ref "C3") (pin "2") (pinfunction "2_2") (pintype "passive"))
      (node (ref "C4") (pin "2") (pinfunction "2_2") (pintype "passive"))
      (node (ref "C5") (pin "2") (pinfunction "2_2") (pintype "passive"))
      (node (ref "C6") (pin "2") (pinfunction "2_2") (pintype "passive"))
      (node (ref "C7") (pin "2") (pinfunction "2_2") (pintype "passive"))
      (node (ref "C8") (pin "1") (pinfunction "1_1") (pintype "passive"))
      (node (ref "C9") (pin "1") (pinfunction "1_1") (pintype "passive"))
      (node (ref "D1") (pin "A") (pinfunction "A_A") (pintype "passive"))
      (node (ref "G1") (pin "-") (pinfunction "-_-") (pintype "passive"))
      (node (ref "IC1") (pin "2") (pinfunction "GND_2") (pintype "passive"))
      (node (ref "IC2") (pin "22") (pinfunction "GND_22") (pintype "power_in"))
      (node (ref "IC2") (pin "8") (pinfunction "GND_8") (pintype "power_in"))
      (node (ref "IC3") (pin "2") (pinfunction "GND_2") (pintype "passive"))
      (node (ref "IC4") (pin "3") (pinfunction "GND_3") (pintype "power_in"))
      (node (ref "IC4") (pin "5") (pinfunction "ON/OFF_5") (pintype "bidirectional"))
      (node (ref "IC5") (pin "3") (pinfunction "GND_3") (pintype "power_in"))
      (node (ref "IC6") (pin "11") (pinfunction "I_11") (pintype "input"))
      (node (ref "IC6") (pin "14") (pinfunction "I_14") (pintype "input"))
      (node (ref "IC6") (pin "8") (pinfunction "VSS_8") (pintype "power_in"))
      (node (ref "IC7") (pin "4") (pinfunction "GND_4") (pintype "bidirectional"))
      (node (ref "ISP") (pin "10") (pinfunction "10_10") (pintype "passive"))
      (node (ref "ISP") (pin "3") (pinfunction "3_3") (pintype "passive"))
      (node (ref "ISP") (pin "8") (pinfunction "8_8") (pintype "passive"))
      (node (ref "LED1") (pin "K") (pinfunction "C_K") (pintype "passive"))
      (node (ref "LED2") (pin "K") (pinfunction "C_K") (pintype "passive"))
      (node (ref "LED3") (pin "K") (pinfunction "C_K") (pintype "passive"))
      (node (ref "LED4") (pin "K") (pinfunction "C_K") (pintype "passive"))
      (node (ref "LED7") (pin "K") (pinfunction "C_K") (pintype "passive"))
      (node (ref "M1") (pin "1") (pinfunction "GND_1") (pintype "power_in"))
      (node (ref "PWR1") (pin "-") (pinfunction "-_-") (pintype "passive"))
      (node (ref "PWR1") (pin "--") (pinfunction "--_--") (pintype "passive"))
      (node (ref "R14") (pin "1") (pinfunction "1_1") (pintype "passive"))
      (node (ref "R22") (pin "2") (pinfunction "2_2") (pintype "passive"))
      (node (ref "R28") (pin "1") (pinfunction "1_1") (pintype "passive"))
      (node (ref "R9") (pin "1") (pinfunction "1_1") (pintype "passive"))
      (node (ref "RESET") (pin "1") (pinfunction "S_1") (pintype "passive"))
      (node (ref "RESET") (pin "2") (pinfunction "S1_2") (pintype "passive"))
      (node (ref "SDCARD") (pin "6") (pinfunction "VSS_6") (pintype "bidirectional"))
      (node (ref "SDCARD") (pin "G1") (pinfunction "GND_G1") (pintype "bidirectional"))
      (node (ref "SDCARD") (pin "G2") (pinfunction "GND_G2") (pintype "bidirectional"))
      (node (ref "SDCARD") (pin "G3") (pinfunction "GND_G3") (pintype "bidirectional"))
      (node (ref "SDCARD") (pin "G4") (pinfunction "GND_G4") (pintype "bidirectional"))
      (node (ref "SIMHOLDER") (pin "6") (pinfunction "GND_6") (pintype "bidirectional"))
      (node (ref "T1") (pin "1") (pinfunction "E_1") (pintype "passive"))
      (node (ref "T2") (pin "1") (pinfunction "E_1") (pintype "passive"))
      (node (ref "T3") (pin "1") (pinfunction "E_1") (pintype "passive"))
      (node (ref "U2") (pin "17") (pinfunction "GND_17") (pintype "power_in"))
      (node (ref "U2") (pin "18") (pinfunction "GND_18") (pintype "power_in"))
      (node (ref "U2") (pin "29") (pinfunction "GND_29") (pintype "power_in"))
      (node (ref "U2") (pin "39") (pinfunction "GND_39") (pintype "power_in"))
      (node (ref "U2") (pin "45") (pinfunction "GND_45") (pintype "power_in"))
      (node (ref "U2") (pin "46") (pinfunction "GND_46") (pintype "power_in"))
      (node (ref "U2") (pin "53") (pinfunction "GND_53") (pintype "power_in"))
      (node (ref "U2") (pin "54") (pinfunction "GND_54") (pintype "power_in"))
      (node (ref "U2") (pin "58") (pinfunction "GND_58") (pintype "power_in"))
      (node (ref "U2") (pin "59") (pinfunction "GND_59") (pintype "power_in"))
      (node (ref "U2") (pin "61") (pinfunction "GND_61") (pintype "power_in"))
      (node (ref "U2") (pin "62") (pinfunction "GND_62") (pintype "power_in"))
      (node (ref "U2") (pin "63") (pinfunction "GND_63") (pintype "power_in"))
      (node (ref "U2") (pin "64") (pinfunction "GND_64") (pintype "power_in"))
      (node (ref "U2") (pin "65") (pinfunction "GND_65") (pintype "power_in"))
      (node (ref "X1") (pin "2") (pinfunction "2_2") (pintype "passive"))
      (node (ref "X1") (pin "3") (pinfunction "2_3") (pintype "passive"))
      (node (ref "X1") (pin "4") (pinfunction "2_4") (pintype "passive"))
      (node (ref "X1") (pin "5") (pinfunction "2_5") (pintype "passive"))
    )
    (net (code "48") (name "Net-(D2-PadA)") (class "Default")
      (node (ref "D2") (pin "A") (pinfunction "A_A") (pintype "passive"))
      (node (ref "PWR1") (pin "+") (pinfunction "+_+") (pintype "passive"))
    )
    (net (code "49") (name "Net-(IC2-AREF)") (class "Default")
      (node (ref "C4") (pin "1") (pinfunction "1_1") (pintype "passive"))
      (node (ref "IC2") (pin "21") (pinfunction "AREF_21") (pintype "passive"))
    )
    (net (code "50") (name "Net-(IC2-PB6(XTAL1{slash}TOSC1))") (class "Default")
      (node (ref "C8") (pin "2") (pinfunction "2_2") (pintype "passive"))
      (node (ref "IC2") (pin "9") (pinfunction "PB6(XTAL1/TOSC1)_9") (pintype "bidirectional"))
      (node (ref "Q2") (pin "1") (pinfunction "1_1") (pintype "passive"))
    )
    (net (code "51") (name "Net-(IC2-PB7(XTAL2{slash}TOSC2))") (class "Default")
      (node (ref "C12") (pin "2") (pinfunction "2_2") (pintype "passive"))
      (node (ref "IC2") (pin "10") (pinfunction "PB7(XTAL2/TOSC2)_10") (pintype "bidirectional"))
      (node (ref "Q2") (pin "2") (pinfunction "2_2") (pintype "passive"))
    )
    (net (code "52") (name "Net-(IC4-FEEDBACK)") (class "Default")
      (node (ref "IC4") (pin "4") (pinfunction "FEEDBACK_4") (pintype "bidirectional"))
      (node (ref "R22") (pin "1") (pinfunction "1_1") (pintype "passive"))
      (node (ref "R8") (pin "2") (pinfunction "2_2") (pintype "passive"))
    )
    (net (code "53") (name "Net-(IC4-OUTPUT)") (class "Default")
      (node (ref "D1") (pin "C") (pinfunction "C_C") (pintype "passive"))
      (node (ref "IC4") (pin "2") (pinfunction "OUTPUT_2") (pintype "output"))
      (node (ref "L1") (pin "1") (pinfunction "1_1") (pintype "passive"))
    )
    (net (code "54") (name "Net-(IC6A-O)") (class "Default")
      (node (ref "IC6") (pin "2") (pinfunction "O_2") (pintype "output"))
      (node (ref "R16") (pin "2") (pinfunction "2_2") (pintype "passive"))
      (node (ref "SDCARD") (pin "2") (pinfunction "CD/DAT3/CS_2") (pintype "bidirectional"))
    )
    (net (code "55") (name "Net-(IC6B-O)") (class "Default")
      (node (ref "IC6") (pin "4") (pinfunction "O_4") (pintype "output"))
      (node (ref "SDCARD") (pin "3") (pinfunction "CMD/DI_3") (pintype "bidirectional"))
    )
    (net (code "56") (name "Net-(IC6C-O)") (class "Default")
      (node (ref "IC6") (pin "6") (pinfunction "O_6") (pintype "output"))
      (node (ref "SDCARD") (pin "5") (pinfunction "CLK/SCLK_5") (pintype "bidirectional"))
    )
    (net (code "57") (name "Net-(IC6D-O)") (class "Default")
      (node (ref "IC6") (pin "10") (pinfunction "O_10") (pintype "output"))
      (node (ref "LED8") (pin "A") (pinfunction "A_A") (pintype "passive"))
    )
    (net (code "58") (name "Net-(IC7-VBATT)") (class "Default")
      (node (ref "G1") (pin "+") (pinfunction "+_+") (pintype "passive"))
      (node (ref "IC7") (pin "3") (pinfunction "VBATT_3") (pintype "bidirectional"))
    )
    (net (code "59") (name "Net-(IC7-X1)") (class "Default")
      (node (ref "IC7") (pin "1") (pinfunction "X1_1") (pintype "bidirectional"))
      (node (ref "Q1") (pin "2") (pinfunction "2_2") (pintype "passive"))
    )
    (net (code "60") (name "Net-(IC7-X2)") (class "Default")
      (node (ref "IC7") (pin "2") (pinfunction "X2_2") (pintype "bidirectional"))
      (node (ref "Q1") (pin "1") (pinfunction "1_1") (pintype "passive"))
    )
    (net (code "61") (name "Net-(LED1-PadA)") (class "Default")
      (node (ref "LED1") (pin "A") (pinfunction "A_A") (pintype "passive"))
      (node (ref "R3") (pin "1") (pinfunction "1_1") (pintype "passive"))
    )
    (net (code "62") (name "Net-(LED2-PadA)") (class "Default")
      (node (ref "LED2") (pin "A") (pinfunction "A_A") (pintype "passive"))
      (node (ref "R26") (pin "1") (pinfunction "1_1") (pintype "passive"))
    )
    (net (code "63") (name "Net-(LED3-PadA)") (class "Default")
      (node (ref "LED3") (pin "A") (pinfunction "A_A") (pintype "passive"))
      (node (ref "R30") (pin "1") (pinfunction "1_1") (pintype "passive"))
    )
    (net (code "64") (name "Net-(LED4-PadA)") (class "Default")
      (node (ref "LED4") (pin "A") (pinfunction "A_A") (pintype "passive"))
      (node (ref "R31") (pin "1") (pinfunction "1_1") (pintype "passive"))
    )
    (net (code "65") (name "Net-(LED5-C)") (class "Default")
      (node (ref "LED5") (pin "K") (pinfunction "C_K") (pintype "passive"))
      (node (ref "R29") (pin "1") (pinfunction "1_1") (pintype "passive"))
    )
    (net (code "66") (name "Net-(LED6-C)") (class "Default")
      (node (ref "LED6") (pin "K") (pinfunction "C_K") (pintype "passive"))
      (node (ref "R15") (pin "1") (pinfunction "1_1") (pintype "passive"))
    )
    (net (code "67") (name "Net-(LED7-PadA)") (class "Default")
      (node (ref "LED7") (pin "A") (pinfunction "A_A") (pintype "passive"))
      (node (ref "R11") (pin "1") (pinfunction "1_1") (pintype "passive"))
    )
    (net (code "68") (name "Net-(LED8-C)") (class "Default")
      (node (ref "LED8") (pin "K") (pinfunction "C_K") (pintype "passive"))
      (node (ref "R16") (pin "1") (pinfunction "1_1") (pintype "passive"))
    )
    (net (code "69") (name "Net-(SIMHOLDER-CLK)") (class "Default")
      (node (ref "R17") (pin "1") (pinfunction "1_1") (pintype "passive"))
      (node (ref "SIMHOLDER") (pin "3") (pinfunction "CLK_3") (pintype "bidirectional"))
    )
    (net (code "70") (name "Net-(SIMHOLDER-I{slash}O)") (class "Default")
      (node (ref "R27") (pin "2") (pinfunction "2_2") (pintype "passive"))
      (node (ref "SIMHOLDER") (pin "4") (pinfunction "I/O_4") (pintype "bidirectional"))
    )
    (net (code "71") (name "Net-(SIMHOLDER-RST)") (class "Default")
      (node (ref "R18") (pin "1") (pinfunction "1_1") (pintype "passive"))
      (node (ref "SIMHOLDER") (pin "2") (pinfunction "RST_2") (pintype "bidirectional"))
    )
    (net (code "72") (name "Net-(T1-B)") (class "Default")
      (node (ref "R19") (pin "1") (pinfunction "1_1") (pintype "passive"))
      (node (ref "R28") (pin "2") (pinfunction "2_2") (pintype "passive"))
      (node (ref "T1") (pin "2") (pinfunction "B_2") (pintype "passive"))
    )
    (net (code "73") (name "Net-(T2-B)") (class "Default")
      (node (ref "R13") (pin "1") (pinfunction "1_1") (pintype "passive"))
      (node (ref "R14") (pin "2") (pinfunction "2_2") (pintype "passive"))
      (node (ref "T2") (pin "2") (pinfunction "B_2") (pintype "passive"))
    )
    (net (code "74") (name "Net-(T3-B)") (class "Default")
      (node (ref "R12") (pin "2") (pinfunction "2_2") (pintype "passive"))
      (node (ref "R9") (pin "2") (pinfunction "2_2") (pintype "passive"))
      (node (ref "T3") (pin "2") (pinfunction "B_2") (pintype "passive"))
    )
    (net (code "75") (name "Net-(U2-NRESET)") (class "Default")
      (node (ref "C20") (pin "2") (pinfunction "2_2") (pintype "passive"))
      (node (ref "U2") (pin "16") (pinfunction "NRESET_16") (pintype "input"))
    )
    (net (code "76") (name "Net-(U2-VRTC)") (class "Default")
      (node (ref "C16") (pin "2") (pinfunction "2_2") (pintype "passive"))
      (node (ref "U2") (pin "26") (pinfunction "VRTC_26") (pintype "bidirectional"))
    )
    (net (code "77") (name "unconnected-(IC2-PC3(ADC3)-Pad26)") (class "Default")
      (node (ref "IC2") (pin "26") (pinfunction "PC3(ADC3)_26") (pintype "bidirectional"))
    )
    (net (code "78") (name "unconnected-(IC6E-O-Pad12)") (class "Default")
      (node (ref "IC6") (pin "12") (pinfunction "O_12") (pintype "output"))
    )
    (net (code "79") (name "unconnected-(IC6F-O-Pad15)") (class "Default")
      (node (ref "IC6") (pin "15") (pinfunction "O_15") (pintype "output"))
    )
    (net (code "80") (name "unconnected-(IC7-SQW-Pad7)") (class "Default")
      (node (ref "IC7") (pin "7") (pinfunction "SQW_7") (pintype "bidirectional"))
    )
    (net (code "81") (name "unconnected-(SDCARD-DAT1-Pad8)") (class "Default")
      (node (ref "SDCARD") (pin "8") (pinfunction "DAT1_8") (pintype "bidirectional"))
    )
    (net (code "82") (name "unconnected-(SDCARD-DAT2-Pad1)") (class "Default")
      (node (ref "SDCARD") (pin "1") (pinfunction "DAT2_1") (pintype "bidirectional"))
    )
    (net (code "83") (name "unconnected-(SIMHOLDER-VPP-Pad5)") (class "Default")
      (node (ref "SIMHOLDER") (pin "5") (pinfunction "VPP_5") (pintype "bidirectional"))
    )
    (net (code "84") (name "unconnected-(U2-ADC-Pad25)") (class "Default")
      (node (ref "U2") (pin "25") (pinfunction "ADC_25") (pintype "input"))
    )
    (net (code "85") (name "unconnected-(U2-CTS-Pad7)") (class "Default")
      (node (ref "U2") (pin "7") (pinfunction "CTS_7") (pintype "output"))
    )
    (net (code "86") (name "unconnected-(U2-DCD-Pad5)") (class "Default")
      (node (ref "U2") (pin "5") (pinfunction "DCD_5") (pintype "output"))
    )
    (net (code "87") (name "unconnected-(U2-DISP_CLK-Pad11)") (class "Default")
      (node (ref "U2") (pin "11") (pinfunction "DISP_CLK_11") (pintype "output"))
    )
    (net (code "88") (name "unconnected-(U2-DISP_CS-Pad14)") (class "Default")
      (node (ref "U2") (pin "14") (pinfunction "DISP_CS_14") (pintype "output"))
    )
    (net (code "89") (name "unconnected-(U2-DISP_DATA-Pad12)") (class "Default")
      (node (ref "U2") (pin "12") (pinfunction "DISP_DATA_12") (pintype "bidirectional"))
    )
    (net (code "90") (name "unconnected-(U2-DISP_D{slash}C-Pad13)") (class "Default")
      (node (ref "U2") (pin "13") (pinfunction "DISP_D/C_13") (pintype "output"))
    )
    (net (code "91") (name "unconnected-(U2-DSR-Pad6)") (class "Default")
      (node (ref "U2") (pin "6") (pinfunction "DSR_6") (pintype "output"))
    )
    (net (code "92") (name "unconnected-(U2-DTR-Pad3)") (class "Default")
      (node (ref "U2") (pin "3") (pinfunction "DTR_3") (pintype "input"))
    )
    (net (code "93") (name "unconnected-(U2-GPIO1{slash}KBR4-Pad40)") (class "Default")
      (node (ref "U2") (pin "40") (pinfunction "GPIO1/KBR4_40") (pintype "output"))
    )
    (net (code "94") (name "unconnected-(U2-GPIO2{slash}KBR3-Pad41)") (class "Default")
      (node (ref "U2") (pin "41") (pinfunction "GPIO2/KBR3_41") (pintype "output"))
    )
    (net (code "95") (name "unconnected-(U2-GPIO3{slash}KBR2-Pad42)") (class "Default")
      (node (ref "U2") (pin "42") (pinfunction "GPIO3/KBR2_42") (pintype "output"))
    )
    (net (code "96") (name "unconnected-(U2-GPIO4{slash}KBR1-Pad43)") (class "Default")
      (node (ref "U2") (pin "43") (pinfunction "GPIO4/KBR1_43") (pintype "output"))
    )
    (net (code "97") (name "unconnected-(U2-GPIO5{slash}KBR0-Pad44)") (class "Default")
      (node (ref "U2") (pin "44") (pinfunction "GPIO5/KBR0_44") (pintype "output"))
    )
    (net (code "98") (name "unconnected-(U2-GPIO6{slash}KBC4-Pad47)") (class "Default")
      (node (ref "U2") (pin "47") (pinfunction "GPIO6/KBC4_47") (pintype "input"))
    )
    (net (code "99") (name "unconnected-(U2-GPIO7{slash}KBC3-Pad48)") (class "Default")
      (node (ref "U2") (pin "48") (pinfunction "GPIO7/KBC3_48") (pintype "bidirectional"))
    )
    (net (code "100") (name "unconnected-(U2-GPIO8{slash}KBC2-Pad49)") (class "Default")
      (node (ref "U2") (pin "49") (pinfunction "GPIO8/KBC2_49") (pintype "input"))
    )
    (net (code "101") (name "unconnected-(U2-GPIO9{slash}KBC1-Pad50)") (class "Default")
      (node (ref "U2") (pin "50") (pinfunction "GPIO9/KBC1_50") (pintype "input"))
    )
    (net (code "102") (name "unconnected-(U2-GPIO10{slash}KBC0-Pad51)") (class "Default")
      (node (ref "U2") (pin "51") (pinfunction "GPIO10/KBC0_51") (pintype "bidirectional"))
    )
    (net (code "103") (name "unconnected-(U2-GPIO11-Pad67)") (class "Default")
      (node (ref "U2") (pin "67") (pinfunction "GPIO11_67") (pintype "bidirectional"))
    )
    (net (code "104") (name "unconnected-(U2-GPIO12-Pad68)") (class "Default")
      (node (ref "U2") (pin "68") (pinfunction "GPIO12_68") (pintype "bidirectional"))
    )
    (net (code "105") (name "unconnected-(U2-LINEIN_L-Pad24)") (class "Default")
      (node (ref "U2") (pin "24") (pinfunction "LINEIN_L_24") (pintype "input"))
    )
    (net (code "106") (name "unconnected-(U2-LINEIN_R-Pad23)") (class "Default")
      (node (ref "U2") (pin "23") (pinfunction "LINEIN_R_23") (pintype "input"))
    )
    (net (code "107") (name "unconnected-(U2-MIC_N-Pad20)") (class "Default")
      (node (ref "U2") (pin "20") (pinfunction "MIC_N_20") (pintype "input"))
    )
    (net (code "108") (name "unconnected-(U2-MIC_P-Pad19)") (class "Default")
      (node (ref "U2") (pin "19") (pinfunction "MIC_P_19") (pintype "input"))
    )
    (net (code "109") (name "unconnected-(U2-PWM1-Pad35)") (class "Default")
      (node (ref "U2") (pin "35") (pinfunction "PWM1_35") (pintype "output"))
    )
    (net (code "110") (name "unconnected-(U2-PWM2-Pad36)") (class "Default")
      (node (ref "U2") (pin "36") (pinfunction "PWM2_36") (pintype "output"))
    )
    (net (code "111") (name "unconnected-(U2-RI-Pad4)") (class "Default")
      (node (ref "U2") (pin "4") (pinfunction "RI_4") (pintype "output"))
    )
    (net (code "112") (name "unconnected-(U2-RTS-Pad8)") (class "Default")
      (node (ref "U2") (pin "8") (pinfunction "RTS_8") (pintype "input"))
    )
    (net (code "113") (name "unconnected-(U2-SCL-Pad38)") (class "Default")
      (node (ref "U2") (pin "38") (pinfunction "SCL_38") (pintype "output"))
    )
    (net (code "114") (name "unconnected-(U2-SDA-Pad37)") (class "Default")
      (node (ref "U2") (pin "37") (pinfunction "SDA_37") (pintype "bidirectional"))
    )
    (net (code "115") (name "unconnected-(U2-SIM_PRESENCE-Pad34)") (class "Default")
      (node (ref "U2") (pin "34") (pinfunction "SIM_PRESENCE_34") (pintype "input"))
    )
    (net (code "116") (name "unconnected-(U2-SPK_N-Pad22)") (class "Default")
      (node (ref "U2") (pin "22") (pinfunction "SPK_N_22") (pintype "output"))
    )
    (net (code "117") (name "unconnected-(U2-SPK_P-Pad21)") (class "Default")
      (node (ref "U2") (pin "21") (pinfunction "SPK_P_21") (pintype "output"))
    )
  )
)
